# Motors.net
KiCad netlist of a schematic drawn in Altium Designer
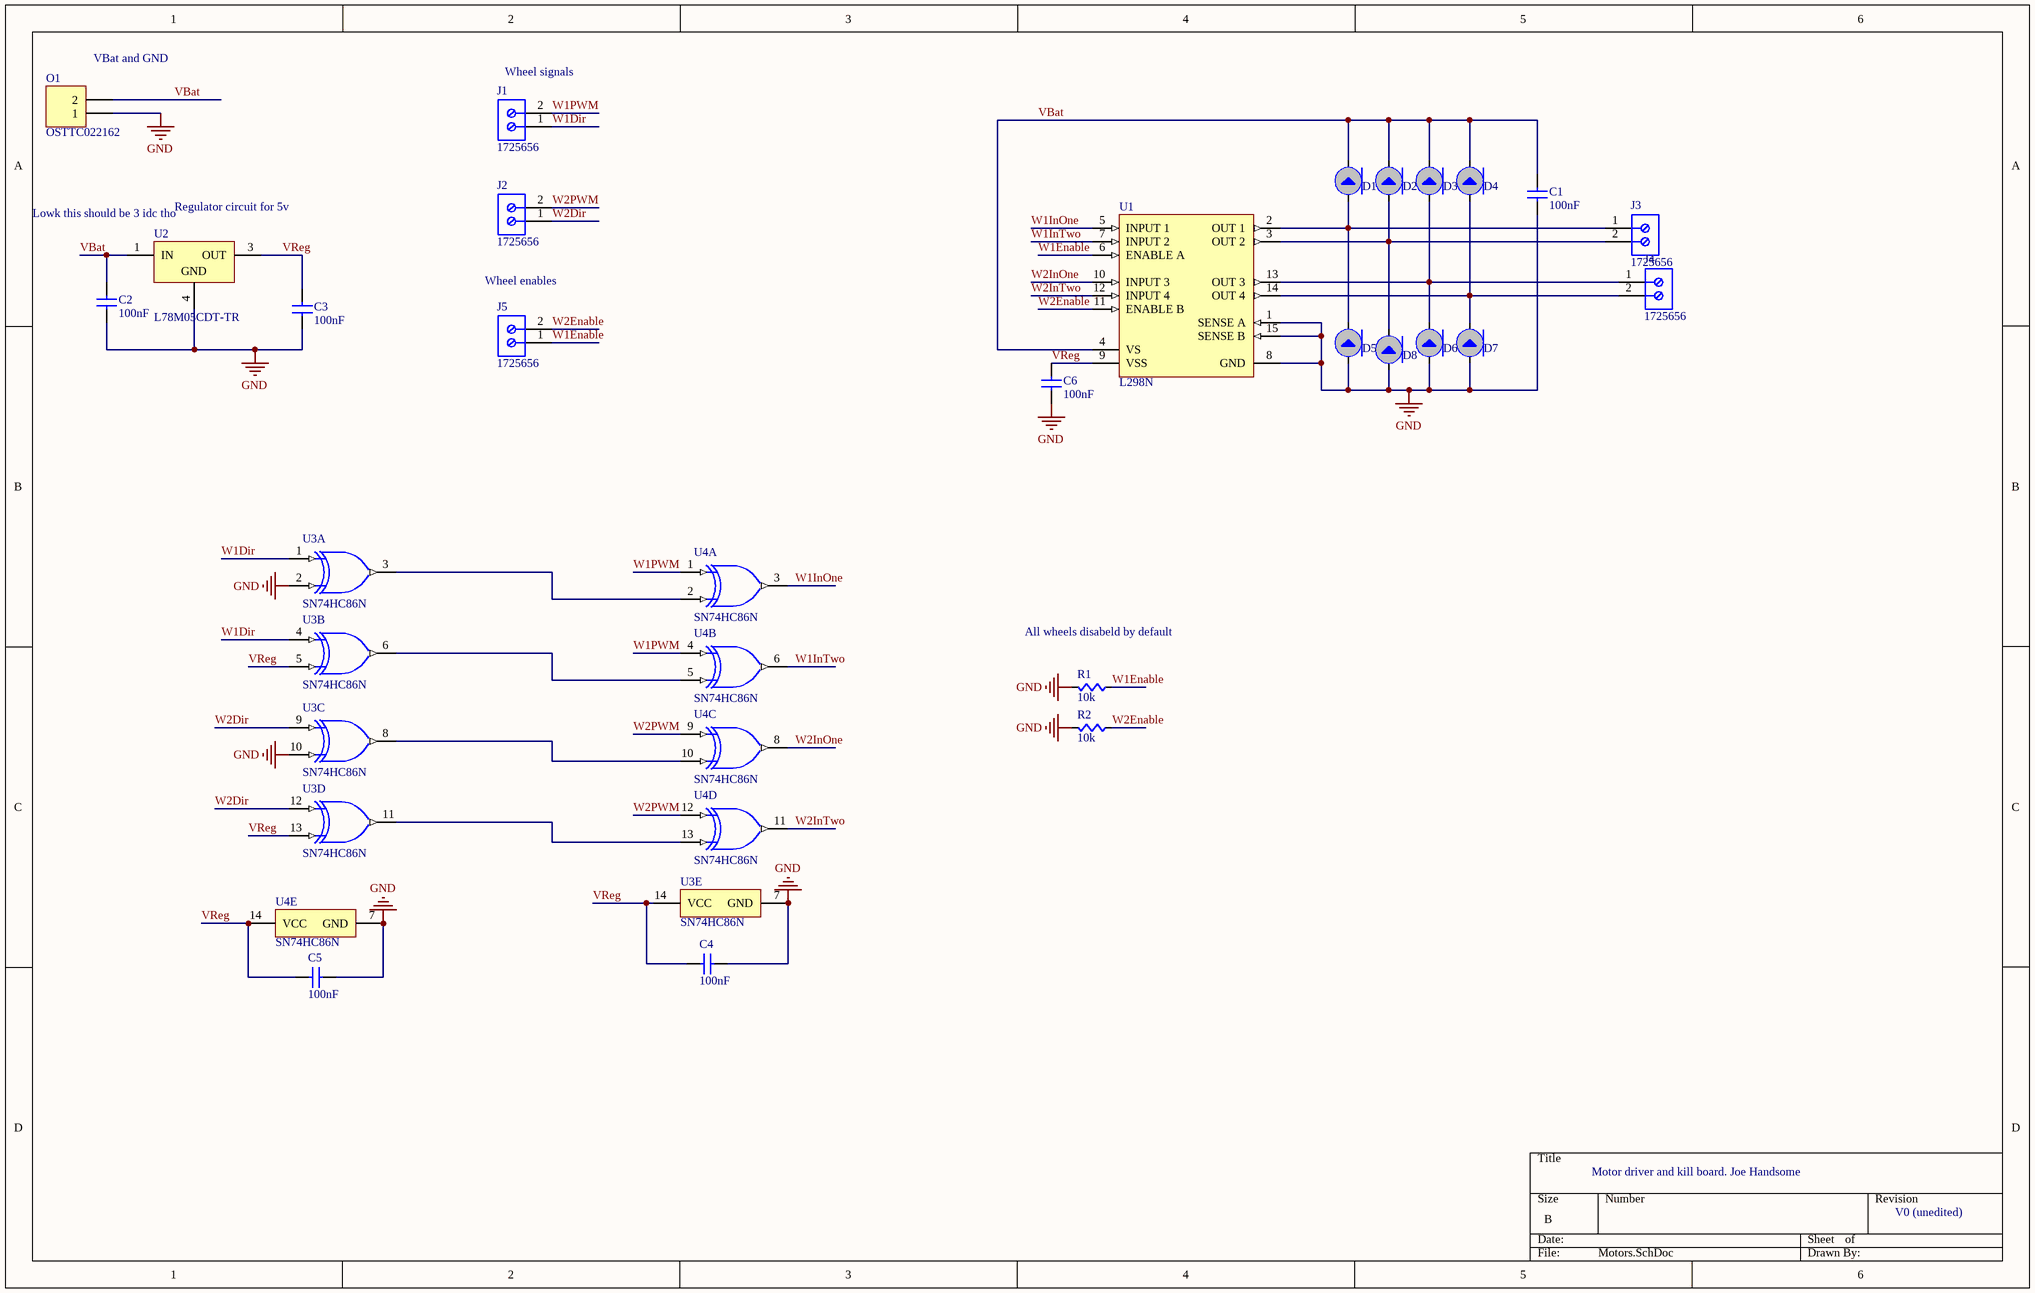
[diagram p0: Motors.SchDoc]

(export (version "E")
  (design (tool "Eeschema 10.0.6"))
  (components
    (comp (ref "C1")
      (value "100nF")
      (footprint "CAPC0603")
      (description "Multilayer Ceramic Capacitor, 0.1 uF, 100 V, ï¿½ 10%, X7R, 0603 [1608 Metric]")
      (fields
        (field (name "MANUFACTURER") "Murata")
        (field (name "MANUFACTURER PART NUMBER") "GCJ188R72A104KA01D")
      )
      (libsource (lib "Passives") (part "Cap"))
    )
    (comp (ref "C2")
      (value "100nF")
      (footprint "CAPC0603")
      (description "Multilayer Ceramic Capacitor, 0.1 uF, 100 V, ï¿½ 10%, X7R, 0603 [1608 Metric]")
      (fields
        (field (name "MANUFACTURER") "Murata")
        (field (name "MANUFACTURER PART NUMBER") "GCJ188R72A104KA01D")
      )
      (libsource (lib "Passives") (part "Cap"))
    )
    (comp (ref "C3")
      (value "100nF")
      (footprint "CAPC0603")
      (description "Multilayer Ceramic Capacitor, 0.1 uF, 100 V, ï¿½ 10%, X7R, 0603 [1608 Metric]")
      (fields
        (field (name "MANUFACTURER") "Murata")
        (field (name "MANUFACTURER PART NUMBER") "GCJ188R72A104KA01D")
      )
      (libsource (lib "Passives") (part "Cap"))
    )
    (comp (ref "C4")
      (value "100nF")
      (footprint "CAPC0603")
      (description "Multilayer Ceramic Capacitor, 0.1 uF, 100 V, ï¿½ 10%, X7R, 0603 [1608 Metric]")
      (fields
        (field (name "MANUFACTURER") "Murata")
        (field (name "MANUFACTURER PART NUMBER") "GCJ188R72A104KA01D")
      )
      (libsource (lib "Passives") (part "Cap"))
    )
    (comp (ref "C5")
      (value "100nF")
      (footprint "CAPC0603")
      (description "Multilayer Ceramic Capacitor, 0.1 uF, 100 V, ï¿½ 10%, X7R, 0603 [1608 Metric]")
      (fields
        (field (name "MANUFACTURER") "Murata")
        (field (name "MANUFACTURER PART NUMBER") "GCJ188R72A104KA01D")
      )
      (libsource (lib "Passives") (part "Cap"))
    )
    (comp (ref "C6")
      (value "100nF")
      (footprint "CAPC0603")
      (description "Multilayer Ceramic Capacitor, 0.1 uF, 100 V, ï¿½ 10%, X7R, 0603 [1608 Metric]")
      (fields
        (field (name "MANUFACTURER") "Murata")
        (field (name "MANUFACTURER PART NUMBER") "GCJ188R72A104KA01D")
      )
      (libsource (lib "Passives") (part "Cap"))
    )
    (comp (ref "D1")
      (value "Diode")
      (footprint "MBRS360SMB")
      (description "Standard Diode Template")
      (libsource (lib "Semiconductors") (part "Diode"))
    )
    (comp (ref "D2")
      (value "Diode")
      (footprint "MBRS360SMB")
      (description "Standard Diode Template")
      (libsource (lib "Semiconductors") (part "Diode"))
    )
    (comp (ref "D3")
      (value "Diode")
      (footprint "MBRS360SMB")
      (description "Standard Diode Template")
      (libsource (lib "Semiconductors") (part "Diode"))
    )
    (comp (ref "D4")
      (value "Diode")
      (footprint "MBRS360SMB")
      (description "Standard Diode Template")
      (libsource (lib "Semiconductors") (part "Diode"))
    )
    (comp (ref "D5")
      (value "Diode")
      (footprint "MBRS360SMB")
      (description "Standard Diode Template")
      (libsource (lib "Semiconductors") (part "Diode"))
    )
    (comp (ref "D6")
      (value "Diode")
      (footprint "MBRS360SMB")
      (description "Standard Diode Template")
      (libsource (lib "Semiconductors") (part "Diode"))
    )
    (comp (ref "D7")
      (value "Diode")
      (footprint "MBRS360SMB")
      (description "Standard Diode Template")
      (libsource (lib "Semiconductors") (part "Diode"))
    )
    (comp (ref "D8")
      (value "Diode")
      (footprint "MBRS360SMB")
      (description "Standard Diode Template")
      (libsource (lib "Semiconductors") (part "Diode"))
    )
    (comp (ref "J1")
      (value "1725656")
      (footprint "PHOE-1725656-2")
      (description "Male Header, Pitch 2.54 mm, 1 x 2 Position, Height 9 mm, Tail Length 3.5 mm")
      (fields (field (name "MANUFACTURER") "Phoenix Contact"))
      (libsource (lib "Altium Content Vault") (part "CN-1P-F-TB2"))
    )
    (comp (ref "J2")
      (value "1725656")
      (footprint "PHOE-1725656-2")
      (description "Male Header, Pitch 2.54 mm, 1 x 2 Position, Height 9 mm, Tail Length 3.5 mm")
      (fields (field (name "MANUFACTURER") "Phoenix Contact"))
      (libsource (lib "Altium Content Vault") (part "CN-1P-F-TB2"))
    )
    (comp (ref "J3")
      (value "1725656")
      (footprint "PHOE-1725656-2")
      (description "Male Header, Pitch 2.54 mm, 1 x 2 Position, Height 9 mm, Tail Length 3.5 mm")
      (fields (field (name "MANUFACTURER") "Phoenix Contact"))
      (libsource (lib "Altium Content Vault") (part "CN-1P-F-TB2"))
    )
    (comp (ref "J4")
      (value "1725656")
      (footprint "PHOE-1725656-2")
      (description "Male Header, Pitch 2.54 mm, 1 x 2 Position, Height 9 mm, Tail Length 3.5 mm")
      (fields (field (name "MANUFACTURER") "Phoenix Contact"))
      (libsource (lib "Altium Content Vault") (part "CN-1P-F-TB2"))
    )
    (comp (ref "J5")
      (value "1725656")
      (footprint "PHOE-1725656-2")
      (description "Male Header, Pitch 2.54 mm, 1 x 2 Position, Height 9 mm, Tail Length 3.5 mm")
      (fields (field (name "MANUFACTURER") "Phoenix Contact"))
      (libsource (lib "Altium Content Vault") (part "CN-1P-F-TB2"))
    )
    (comp (ref "O1")
      (value "OSTTC022162")
      (footprint "high_amp_conn")
      (description "Terminal Block Header 2-Position Top Screw 0.200\" (5.08mm) PC-Pins")
      (fields (field (name "MANUFACTURER") "On-Shore Technology") (field (name "VOLTAGE") "300V"))
      (libsource (lib "Schlib1") (part "OSTTC022162"))
    )
    (comp (ref "R1")
      (value "10k")
      (footprint "RES0603")
      (fields (field (name "Comment") "Res"))
      (libsource (lib "Passives") (part "Res"))
    )
    (comp (ref "R2")
      (value "10k")
      (footprint "RES0603")
      (fields (field (name "Comment") "Res"))
      (libsource (lib "Passives") (part "Res"))
    )
    (comp (ref "U1")
      (value "L298N")
      (footprint "STM-FM-15")
      (description "Dual Full-Bridge Driver, 4.8 to 46 V, -40 to 150 degC, 15-Pin FM (MW 15L), RoHS, Tube")
      (fields (field (name "MANUFACTURER") "STMicroelectronics") (field (name "PARTNUMBER") "L298"))
      (libsource (lib "Altium Content Vault") (part "STM-L298-15"))
    )
    (comp (ref "U2")
      (value "L78M05CDT-TR")
      (footprint "TO-252_L")
      (description "Positive Voltage Regulator, 5V, 3-Pin DPAK, Tape and Reel")
      (libsource (lib "Altium Content Vault") (part "PM-REG-L4940-SOT3"))
    )
    (comp (ref "U3")
      (value "SN74HC86N")
      (footprint "PCBComponent_1")
      (description "Quadruple 2-Input Exclusive-OR Gates, N0014A, TUBE")
      (fields
        (field (name "MANUFACTURER") "Texas Instruments")
        (field (name "GENERIC PART NUMBER") "SN74HC86")
      )
      (libsource (lib "Schlib1") (part "CMP-0778-00109-3"))
    )
    (comp (ref "U4")
      (value "SN74HC86N")
      (footprint "PCBComponent_1")
      (description "Quadruple 2-Input Exclusive-OR Gates, N0014A, TUBE")
      (fields
        (field (name "MANUFACTURER") "Texas Instruments")
        (field (name "GENERIC PART NUMBER") "SN74HC86")
      )
      (libsource (lib "Schlib1") (part "CMP-0778-00109-3"))
    )
  )
  (nets
    (net (code "1") (name "/VBat") (class "Default")
      (node (ref "C1") (pin "1") (pinfunction "A_1") (pintype "passive"))
      (node (ref "C2") (pin "1") (pinfunction "A_1") (pintype "passive"))
      (node (ref "D1") (pin "C") (pinfunction "C_C") (pintype "passive"))
      (node (ref "D2") (pin "C") (pinfunction "C_C") (pintype "passive"))
      (node (ref "D3") (pin "C") (pinfunction "C_C") (pintype "passive"))
      (node (ref "D4") (pin "C") (pinfunction "C_C") (pintype "passive"))
      (node (ref "O1") (pin "2") (pinfunction "2_2") (pintype "passive"))
      (node (ref "U1") (pin "4") (pinfunction "VS_4") (pintype "power_in"))
      (node (ref "U2") (pin "1") (pinfunction "IN_1") (pintype "power_in"))
    )
    (net (code "2") (name "/VReg") (class "Default")
      (node (ref "C3") (pin "1") (pinfunction "A_1") (pintype "passive"))
      (node (ref "C4") (pin "1") (pinfunction "A_1") (pintype "passive"))
      (node (ref "C5") (pin "1") (pinfunction "A_1") (pintype "passive"))
      (node (ref "C6") (pin "1") (pinfunction "A_1") (pintype "passive"))
      (node (ref "U1") (pin "9") (pinfunction "VSS_9") (pintype "power_in"))
      (node (ref "U2") (pin "3") (pinfunction "OUT_3") (pintype "power_in"))
      (node (ref "U3") (pin "13") (pinfunction "4B_13") (pintype "input"))
      (node (ref "U3") (pin "14") (pinfunction "VCC_14") (pintype "power_in"))
      (node (ref "U3") (pin "5") (pinfunction "2B_5") (pintype "input"))
      (node (ref "U4") (pin "14") (pinfunction "VCC_14") (pintype "power_in"))
    )
    (net (code "3") (name "/W1Dir") (class "Default")
      (node (ref "J1") (pin "1") (pinfunction "1_1") (pintype "passive"))
      (node (ref "U3") (pin "1") (pinfunction "1A_1") (pintype "input"))
      (node (ref "U3") (pin "4") (pinfunction "2A_4") (pintype "input"))
    )
    (net (code "4") (name "/W1Enable") (class "Default")
      (node (ref "J5") (pin "1") (pinfunction "1_1") (pintype "passive"))
      (node (ref "R1") (pin "2") (pinfunction "B_2") (pintype "passive"))
      (node (ref "U1") (pin "6") (pinfunction "ENABLE_A_6") (pintype "input"))
    )
    (net (code "5") (name "/W1InOne") (class "Default")
      (node (ref "U1") (pin "5") (pinfunction "INPUT_1_5") (pintype "input"))
      (node (ref "U4") (pin "3") (pinfunction "1Y_3") (pintype "output"))
    )
    (net (code "6") (name "/W1InTwo") (class "Default")
      (node (ref "U1") (pin "7") (pinfunction "INPUT_2_7") (pintype "input"))
      (node (ref "U4") (pin "6") (pinfunction "2Y_6") (pintype "output"))
    )
    (net (code "7") (name "/W1PWM") (class "Default")
      (node (ref "J1") (pin "2") (pinfunction "2_2") (pintype "passive"))
      (node (ref "U4") (pin "1") (pinfunction "1A_1") (pintype "input"))
      (node (ref "U4") (pin "4") (pinfunction "2A_4") (pintype "input"))
    )
    (net (code "8") (name "/W2Dir") (class "Default")
      (node (ref "J2") (pin "1") (pinfunction "1_1") (pintype "passive"))
      (node (ref "U3") (pin "12") (pinfunction "4A_12") (pintype "input"))
      (node (ref "U3") (pin "9") (pinfunction "3A_9") (pintype "input"))
    )
    (net (code "9") (name "/W2Enable") (class "Default")
      (node (ref "J5") (pin "2") (pinfunction "2_2") (pintype "passive"))
      (node (ref "R2") (pin "2") (pinfunction "B_2") (pintype "passive"))
      (node (ref "U1") (pin "11") (pinfunction "ENABLE_B_11") (pintype "input"))
    )
    (net (code "10") (name "/W2InOne") (class "Default")
      (node (ref "U1") (pin "10") (pinfunction "INPUT_3_10") (pintype "input"))
      (node (ref "U4") (pin "8") (pinfunction "3Y_8") (pintype "output"))
    )
    (net (code "11") (name "/W2InTwo") (class "Default")
      (node (ref "U1") (pin "12") (pinfunction "INPUT_4_12") (pintype "input"))
      (node (ref "U4") (pin "11") (pinfunction "4Y_11") (pintype "output"))
    )
    (net (code "12") (name "/W2PWM") (class "Default")
      (node (ref "J2") (pin "2") (pinfunction "2_2") (pintype "passive"))
      (node (ref "U4") (pin "12") (pinfunction "4A_12") (pintype "input"))
      (node (ref "U4") (pin "9") (pinfunction "3A_9") (pintype "input"))
    )
    (net (code "13") (name "GND") (class "Default")
      (node (ref "C1") (pin "2") (pinfunction "B_2") (pintype "passive"))
      (node (ref "C2") (pin "2") (pinfunction "B_2") (pintype "passive"))
      (node (ref "C3") (pin "2") (pinfunction "B_2") (pintype "passive"))
      (node (ref "C4") (pin "2") (pinfunction "B_2") (pintype "passive"))
      (node (ref "C5") (pin "2") (pinfunction "B_2") (pintype "passive"))
      (node (ref "C6") (pin "2") (pinfunction "B_2") (pintype "passive"))
      (node (ref "D5") (pin "A") (pinfunction "A_A") (pintype "passive"))
      (node (ref "D6") (pin "A") (pinfunction "A_A") (pintype "passive"))
      (node (ref "D7") (pin "A") (pinfunction "A_A") (pintype "passive"))
      (node (ref "D8") (pin "A") (pinfunction "A_A") (pintype "passive"))
      (node (ref "O1") (pin "1") (pinfunction "1_1") (pintype "passive"))
      (node (ref "R1") (pin "1") (pinfunction "A_1") (pintype "passive"))
      (node (ref "R2") (pin "1") (pinfunction "A_1") (pintype "passive"))
      (node (ref "U1") (pin "1") (pinfunction "SENSE_A_1") (pintype "input"))
      (node (ref "U1") (pin "15") (pinfunction "SENSE_B_15") (pintype "input"))
      (node (ref "U1") (pin "8") (pinfunction "GND_8") (pintype "power_in"))
      (node (ref "U2") (pin "4") (pinfunction "GND_4") (pintype "power_in"))
      (node (ref "U3") (pin "10") (pinfunction "3B_10") (pintype "input"))
      (node (ref "U3") (pin "2") (pinfunction "1B_2") (pintype "input"))
      (node (ref "U3") (pin "7") (pinfunction "GND_7") (pintype "power_in"))
      (node (ref "U4") (pin "7") (pinfunction "GND_7") (pintype "power_in"))
    )
    (net (code "14") (name "Net-(U1-OUT_1)") (class "Default")
      (node (ref "D1") (pin "A") (pinfunction "A_A") (pintype "passive"))
      (node (ref "D5") (pin "C") (pinfunction "C_C") (pintype "passive"))
      (node (ref "J3") (pin "1") (pinfunction "1_1") (pintype "passive"))
      (node (ref "U1") (pin "2") (pinfunction "OUT_1_2") (pintype "output"))
    )
    (net (code "15") (name "Net-(U1-OUT_2)") (class "Default")
      (node (ref "D2") (pin "A") (pinfunction "A_A") (pintype "passive"))
      (node (ref "D8") (pin "C") (pinfunction "C_C") (pintype "passive"))
      (node (ref "J3") (pin "2") (pinfunction "2_2") (pintype "passive"))
      (node (ref "U1") (pin "3") (pinfunction "OUT_2_3") (pintype "output"))
    )
    (net (code "16") (name "Net-(U1-OUT_3)") (class "Default")
      (node (ref "D3") (pin "A") (pinfunction "A_A") (pintype "passive"))
      (node (ref "D6") (pin "C") (pinfunction "C_C") (pintype "passive"))
      (node (ref "J4") (pin "1") (pinfunction "1_1") (pintype "passive"))
      (node (ref "U1") (pin "13") (pinfunction "OUT_3_13") (pintype "output"))
    )
    (net (code "17") (name "Net-(U1-OUT_4)") (class "Default")
      (node (ref "D4") (pin "A") (pinfunction "A_A") (pintype "passive"))
      (node (ref "D7") (pin "C") (pinfunction "C_C") (pintype "passive"))
      (node (ref "J4") (pin "2") (pinfunction "2_2") (pintype "passive"))
      (node (ref "U1") (pin "14") (pinfunction "OUT_4_14") (pintype "output"))
    )
    (net (code "18") (name "Net-(U3A-1Y)") (class "Default")
      (node (ref "U3") (pin "3") (pinfunction "1Y_3") (pintype "output"))
      (node (ref "U4") (pin "2") (pinfunction "1B_2") (pintype "input"))
    )
    (net (code "19") (name "Net-(U3B-2Y)") (class "Default")
      (node (ref "U3") (pin "6") (pinfunction "2Y_6") (pintype "output"))
      (node (ref "U4") (pin "5") (pinfunction "2B_5") (pintype "input"))
    )
    (net (code "20") (name "Net-(U3C-3Y)") (class "Default")
      (node (ref "U3") (pin "8") (pinfunction "3Y_8") (pintype "output"))
      (node (ref "U4") (pin "10") (pinfunction "3B_10") (pintype "input"))
    )
    (net (code "21") (name "Net-(U3D-4Y)") (class "Default")
      (node (ref "U3") (pin "11") (pinfunction "4Y_11") (pintype "output"))
      (node (ref "U4") (pin "13") (pinfunction "4B_13") (pintype "input"))
    )
  )
)
